# SD_Card.net
KiCad netlist of a schematic drawn in Altium Designer
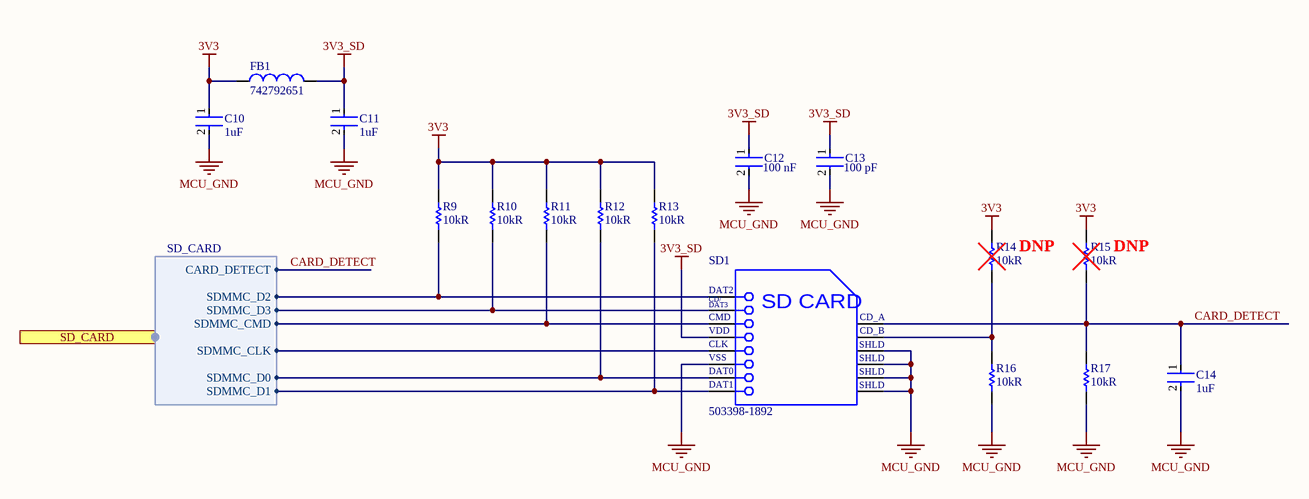
[diagram p0: SD_Card.SchDoc]

(export (version "E")
  (design (tool "Eeschema 10.0.6"))
  (components
    (comp (ref "C10")
      (value "C1608X5R1H105K080AB")
      (footprint "FP-C1608-080-0_1-IPC_B")
      (description "Multilayer Ceramic Capacitors 1μF ±10% 50V X5R SMD 0603")
      (fields
        (field (name "VOLTAGE") "50V")
        (field (name "CAPACITANCE") "1uF")
        (field (name "TOLERANCE") "10%")
      )
      (libsource (lib "Altium Content Vault") (part "236180d848d6139a670b325ea6854c9"))
    )
    (comp (ref "C11")
      (value "C1608X5R1H105K080AB")
      (footprint "FP-C1608-080-0_1-IPC_B")
      (description "Multilayer Ceramic Capacitors 1μF ±10% 50V X5R SMD 0603")
      (fields
        (field (name "VOLTAGE") "50V")
        (field (name "CAPACITANCE") "1uF")
        (field (name "TOLERANCE") "10%")
      )
      (libsource (lib "Altium Content Vault") (part "236180d848d6139a670b325ea6854c9"))
    )
    (comp (ref "C12")
      (value "CC0603KRX7R7BB104")
      (footprint "FP-CC0603-DA-MFG")
      (description "CAP CER 0.1UF 16V X7R 0603")
      (fields
        (field (name "OCTOPART") "https://octopart.com/cc0603krx7r7bb104-yageo-192941")
        (field (name "TOLERANCE") "0.1")
        (field (name "CAPACITANCE") "100 nF")
      )
      (libsource (lib "Altium Content Vault") (part "11868f565c42a9108669ba33697ecf6"))
    )
    (comp (ref "C13")
      (value "100 pF")
      (footprint "FP-C0603C-CF-MFG")
      (description "CAP CER 100PF 50V C0G/NP0 0603")
      (fields (field (name "MANUFACTURER PART NUMBER") "C0603C101J5GACTU") (field (name "TOLERANCE") "0.05"))
      (libsource (lib "Altium Content Vault") (part "b4654b650e69147ec39a6b967a45e02"))
    )
    (comp (ref "C14")
      (value "C1608X5R1H105K080AB")
      (footprint "FP-C1608-080-0_1-IPC_B")
      (description "Multilayer Ceramic Capacitors 1μF ±10% 50V X5R SMD 0603")
      (fields
        (field (name "VOLTAGE") "50V")
        (field (name "CAPACITANCE") "1uF")
        (field (name "TOLERANCE") "10%")
      )
      (libsource (lib "Altium Content Vault") (part "236180d848d6139a670b325ea6854c9"))
    )
    (comp (ref "FB1")
      (value "742792651")
      (footprint "WE-CBF_0603_L1.6W0.8H0.8_HC")
      (fields (field (name "TOLERANCE") "25%"))
      (libsource (lib "Altium Content Vault") (part "Ferrite"))
    )
    (comp (ref "R9")
      (value "CRCW060310K0FKEA")
      (footprint "RESC1609X50X30NL8T20")
      (description "Chip Resistor, 10 KOhm, +/- 1%, 100 mW, -55 to 155 degC, 0603 (1608 Metric), RoHS, Tape and Reel")
      (fields (field (name "MANUFACTURER") "Vishay Semiconductor") (field (name "RESISTANCE") "10kR"))
      (libsource (lib "Altium Content Vault") (part "RES-2"))
    )
    (comp (ref "R10")
      (value "CRCW060310K0FKEA")
      (footprint "RESC1609X50X30NL8T20")
      (description "Chip Resistor, 10 KOhm, +/- 1%, 100 mW, -55 to 155 degC, 0603 (1608 Metric), RoHS, Tape and Reel")
      (fields (field (name "MANUFACTURER") "Vishay Semiconductor") (field (name "RESISTANCE") "10kR"))
      (libsource (lib "Altium Content Vault") (part "RES-2"))
    )
    (comp (ref "R11")
      (value "CRCW060310K0FKEA")
      (footprint "RESC1609X50X30NL8T20")
      (description "Chip Resistor, 10 KOhm, +/- 1%, 100 mW, -55 to 155 degC, 0603 (1608 Metric), RoHS, Tape and Reel")
      (fields (field (name "MANUFACTURER") "Vishay Semiconductor") (field (name "RESISTANCE") "10kR"))
      (libsource (lib "Altium Content Vault") (part "RES-2"))
    )
    (comp (ref "R12")
      (value "CRCW060310K0FKEA")
      (footprint "RESC1609X50X30NL8T20")
      (description "Chip Resistor, 10 KOhm, +/- 1%, 100 mW, -55 to 155 degC, 0603 (1608 Metric), RoHS, Tape and Reel")
      (fields (field (name "MANUFACTURER") "Vishay Semiconductor") (field (name "RESISTANCE") "10kR"))
      (libsource (lib "Altium Content Vault") (part "RES-2"))
    )
    (comp (ref "R13")
      (value "CRCW060310K0FKEA")
      (footprint "RESC1609X50X30NL8T20")
      (description "Chip Resistor, 10 KOhm, +/- 1%, 100 mW, -55 to 155 degC, 0603 (1608 Metric), RoHS, Tape and Reel")
      (fields (field (name "MANUFACTURER") "Vishay Semiconductor") (field (name "RESISTANCE") "10kR"))
      (libsource (lib "Altium Content Vault") (part "RES-2"))
    )
    (comp (ref "R14")
      (value "CRCW060310K0FKEA")
      (footprint "RESC1609X50X30NL8T20")
      (description "Chip Resistor, 10 KOhm, +/- 1%, 100 mW, -55 to 155 degC, 0603 (1608 Metric), RoHS, Tape and Reel")
      (fields (field (name "MANUFACTURER") "Vishay Semiconductor") (field (name "RESISTANCE") "10kR"))
      (libsource (lib "Altium Content Vault") (part "RES-2"))
    )
    (comp (ref "R15")
      (value "CRCW060310K0FKEA")
      (footprint "RESC1609X50X30NL8T20")
      (description "Chip Resistor, 10 KOhm, +/- 1%, 100 mW, -55 to 155 degC, 0603 (1608 Metric), RoHS, Tape and Reel")
      (fields (field (name "MANUFACTURER") "Vishay Semiconductor") (field (name "RESISTANCE") "10kR"))
      (libsource (lib "Altium Content Vault") (part "RES-2"))
    )
    (comp (ref "R16")
      (value "CRCW060310K0FKEA")
      (footprint "RESC1609X50X30NL8T20")
      (description "Chip Resistor, 10 KOhm, +/- 1%, 100 mW, -55 to 155 degC, 0603 (1608 Metric), RoHS, Tape and Reel")
      (fields (field (name "MANUFACTURER") "Vishay Semiconductor") (field (name "RESISTANCE") "10kR"))
      (libsource (lib "Altium Content Vault") (part "RES-2"))
    )
    (comp (ref "R17")
      (value "CRCW060310K0FKEA")
      (footprint "RESC1609X50X30NL8T20")
      (description "Chip Resistor, 10 KOhm, +/- 1%, 100 mW, -55 to 155 degC, 0603 (1608 Metric), RoHS, Tape and Reel")
      (fields (field (name "MANUFACTURER") "Vishay Semiconductor") (field (name "RESISTANCE") "10kR"))
      (libsource (lib "Altium Content Vault") (part "RES-2"))
    )
    (comp (ref "SD1")
      (value "503398-1892")
      (footprint "MOLX-503398-1892_V")
      (description "Micro SD Connector, Pitch 1.1 mm, 8 Position, Height 1.4 mm, -25 to 85 degC, RoHS, Tape and Reel")
      (fields (field (name "MANUFACTURER") "Molex"))
      (libsource (lib "Altium Content Vault") (part "CN-SD-8-2SW-4S"))
    )
  )
  (nets
    (net (code "2") (name "/CARD_DETECT") (class "Default")
      (node (ref "C14") (pin "1") (pinfunction "1_1") (pintype "passive"))
      (node (ref "R15") (pin "1") (pinfunction "1_1") (pintype "passive"))
      (node (ref "R17") (pin "2") (pinfunction "2_2") (pintype "passive"))
      (node (ref "SD1") (pin "9") (pinfunction "CD_A_9") (pintype "passive"))
    )
    (net (code "3") (name "/SDMMC_CLK") (class "Default")
      (node (ref "SD1") (pin "5") (pinfunction "CLK_5") (pintype "passive"))
    )
    (net (code "4") (name "/SDMMC_CMD") (class "Default")
      (node (ref "R11") (pin "1") (pinfunction "1_1") (pintype "passive"))
      (node (ref "SD1") (pin "3") (pinfunction "CMD_3") (pintype "passive"))
    )
    (net (code "5") (name "/SDMMC_D0") (class "Default")
      (node (ref "R12") (pin "1") (pinfunction "1_1") (pintype "passive"))
      (node (ref "SD1") (pin "7") (pinfunction "DAT0_7") (pintype "passive"))
    )
    (net (code "6") (name "/SDMMC_D1") (class "Default")
      (node (ref "R13") (pin "1") (pinfunction "1_1") (pintype "passive"))
      (node (ref "SD1") (pin "8") (pinfunction "DAT1_8") (pintype "passive"))
    )
    (net (code "7") (name "/SDMMC_D2") (class "Default")
      (node (ref "R9") (pin "1") (pinfunction "1_1") (pintype "passive"))
      (node (ref "SD1") (pin "1") (pinfunction "DAT2_1") (pintype "passive"))
    )
    (net (code "8") (name "/SDMMC_D3") (class "Default")
      (node (ref "R10") (pin "1") (pinfunction "1_1") (pintype "passive"))
      (node (ref "SD1") (pin "2") (pinfunction "CD/DAT3_2") (pintype "passive"))
    )
    (net (code "10") (name "3V3") (class "Default")
      (node (ref "C10") (pin "1") (pinfunction "1_1") (pintype "passive"))
      (node (ref "FB1") (pin "1") (pinfunction "1_1") (pintype "passive"))
      (node (ref "R10") (pin "2") (pinfunction "2_2") (pintype "passive"))
      (node (ref "R11") (pin "2") (pinfunction "2_2") (pintype "passive"))
      (node (ref "R12") (pin "2") (pinfunction "2_2") (pintype "passive"))
      (node (ref "R13") (pin "2") (pinfunction "2_2") (pintype "passive"))
      (node (ref "R14") (pin "2") (pinfunction "2_2") (pintype "passive"))
      (node (ref "R15") (pin "2") (pinfunction "2_2") (pintype "passive"))
      (node (ref "R9") (pin "2") (pinfunction "2_2") (pintype "passive"))
    )
    (net (code "11") (name "3V3_SD") (class "Default")
      (node (ref "C11") (pin "1") (pinfunction "1_1") (pintype "passive"))
      (node (ref "C12") (pin "1") (pinfunction "1_1") (pintype "passive"))
      (node (ref "C13") (pin "1") (pinfunction "1_1") (pintype "passive"))
      (node (ref "FB1") (pin "2") (pinfunction "2_2") (pintype "passive"))
      (node (ref "SD1") (pin "4") (pinfunction "VDD_4") (pintype "passive"))
    )
    (net (code "12") (name "MCU_GND") (class "Default")
      (node (ref "C10") (pin "2") (pinfunction "2_2") (pintype "passive"))
      (node (ref "C11") (pin "2") (pinfunction "2_2") (pintype "passive"))
      (node (ref "C12") (pin "2") (pinfunction "2_2") (pintype "passive"))
      (node (ref "C13") (pin "2") (pinfunction "2_2") (pintype "passive"))
      (node (ref "C14") (pin "2") (pinfunction "2_2") (pintype "passive"))
      (node (ref "R16") (pin "1") (pinfunction "1_1") (pintype "passive"))
      (node (ref "R17") (pin "1") (pinfunction "1_1") (pintype "passive"))
      (node (ref "SD1") (pin "11") (pinfunction "SHLD_11") (pintype "passive"))
      (node (ref "SD1") (pin "12") (pinfunction "SHLD_12") (pintype "passive"))
      (node (ref "SD1") (pin "13") (pinfunction "SHLD_13") (pintype "passive"))
      (node (ref "SD1") (pin "14") (pinfunction "SHLD_14") (pintype "passive"))
      (node (ref "SD1") (pin "6") (pinfunction "VSS_6") (pintype "passive"))
    )
    (net (code "13") (name "Net-(SD1-CD_B)") (class "Default")
      (node (ref "R14") (pin "1") (pinfunction "1_1") (pintype "passive"))
      (node (ref "R16") (pin "2") (pinfunction "2_2") (pintype "passive"))
      (node (ref "SD1") (pin "10") (pinfunction "CD_B_10") (pintype "passive"))
    )
  )
)
